# conector_driver.net
KiCad netlist of a schematic drawn in EAGLE
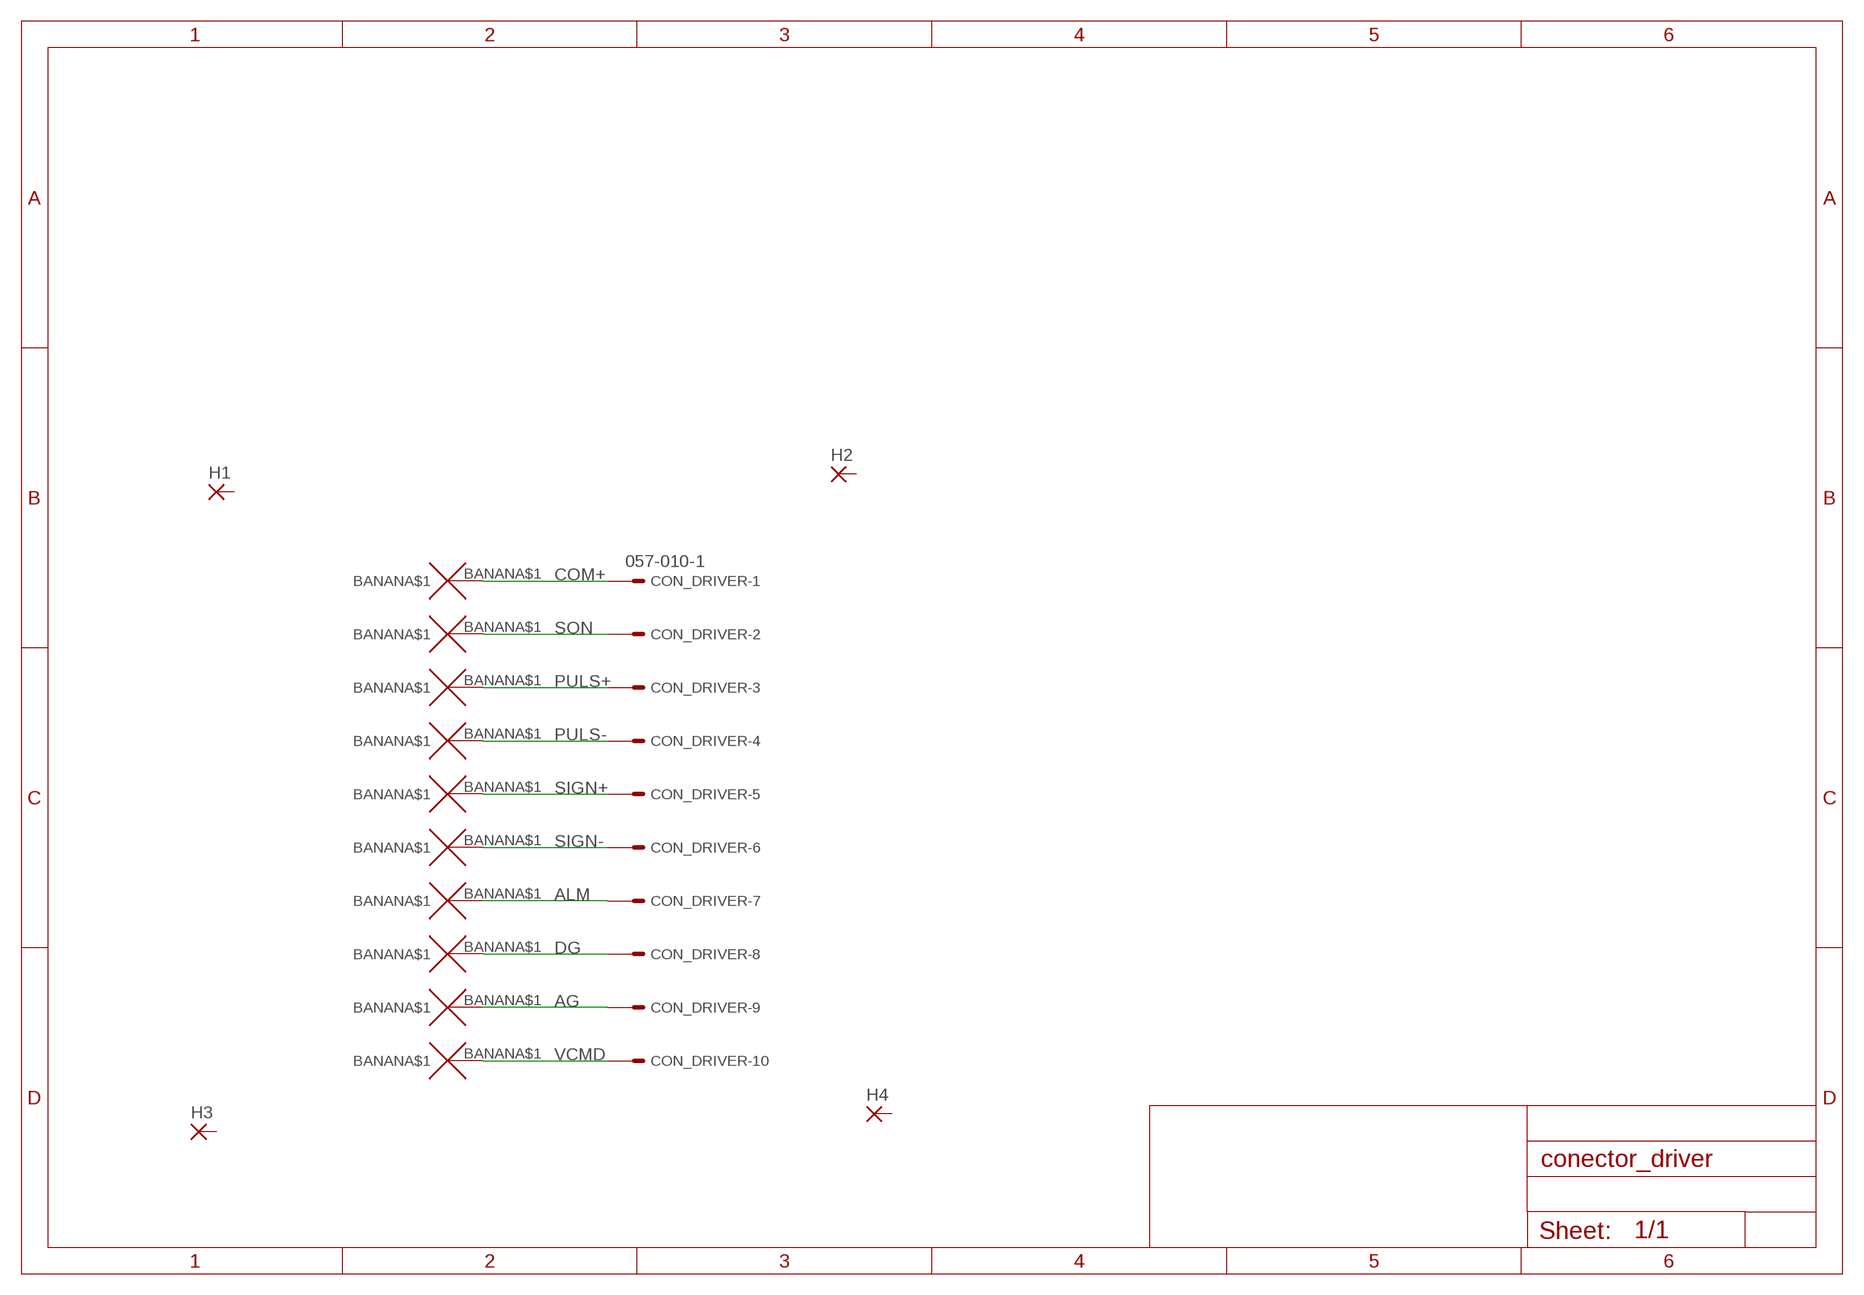
[diagram p0: schematic, sheet 1]

(export (version "E")
  (design (tool "Eeschema 10.0.6"))
  (components
    (comp (ref "AG")
      (value "BANANA")
      (footprint "eagle-import:BANANA")
      (libsource (lib "eagle-import") (part "BANANA"))
    )
    (comp (ref "ALM")
      (value "BANANA")
      (footprint "eagle-import:BANANA")
      (libsource (lib "eagle-import") (part "BANANA"))
    )
    (comp (ref "COM+")
      (value "BANANA")
      (footprint "eagle-import:BANANA")
      (libsource (lib "eagle-import") (part "BANANA"))
    )
    (comp (ref "CON_DRIVER")
      (value "057-010-1")
      (footprint "eagle-import:057-010-1")
      (libsource (lib "eagle-import") (part "057-010-1"))
    )
    (comp (ref "DG")
      (value "BANANA")
      (footprint "eagle-import:BANANA")
      (libsource (lib "eagle-import") (part "BANANA"))
    )
    (comp (ref "H1")
      (value "3,81/1,4")
      (footprint "eagle-import:3,81_1,4")
      (libsource (lib "eagle-import") (part "3,81/1,4"))
    )
    (comp (ref "H2")
      (value "3,81/1,4")
      (footprint "eagle-import:3,81_1,4")
      (libsource (lib "eagle-import") (part "3,81/1,4"))
    )
    (comp (ref "H3")
      (value "3,81/1,4")
      (footprint "eagle-import:3,81_1,4")
      (libsource (lib "eagle-import") (part "3,81/1,4"))
    )
    (comp (ref "H4")
      (value "3,81/1,4")
      (footprint "eagle-import:3,81_1,4")
      (libsource (lib "eagle-import") (part "3,81/1,4"))
    )
    (comp (ref "PULS+")
      (value "BANANA")
      (footprint "eagle-import:BANANA")
      (libsource (lib "eagle-import") (part "BANANA"))
    )
    (comp (ref "PULS-")
      (value "BANANA")
      (footprint "eagle-import:BANANA")
      (libsource (lib "eagle-import") (part "BANANA"))
    )
    (comp (ref "SIGN+")
      (value "BANANA")
      (footprint "eagle-import:BANANA")
      (libsource (lib "eagle-import") (part "BANANA"))
    )
    (comp (ref "SIGN-")
      (value "BANANA")
      (footprint "eagle-import:BANANA")
      (libsource (lib "eagle-import") (part "BANANA"))
    )
    (comp (ref "SON")
      (value "BANANA")
      (footprint "eagle-import:BANANA")
      (libsource (lib "eagle-import") (part "BANANA"))
    )
    (comp (ref "VCMD")
      (value "BANANA")
      (footprint "eagle-import:BANANA")
      (libsource (lib "eagle-import") (part "BANANA"))
    )
  )
  (nets
    (net (code "1") (name "/AG") (class "Default")
      (node (ref "AG") (pin "BANANA$1") (pinfunction "BANANA$1_BANANA$1") (pintype "bidirectional"))
      (node (ref "CON_DRIVER") (pin "9") (pinfunction "S_9") (pintype "passive"))
    )
    (net (code "2") (name "/ALM") (class "Default")
      (node (ref "ALM") (pin "BANANA$1") (pinfunction "BANANA$1_BANANA$1") (pintype "bidirectional"))
      (node (ref "CON_DRIVER") (pin "7") (pinfunction "S_7") (pintype "passive"))
    )
    (net (code "3") (name "/COM+") (class "Default")
      (node (ref "COM+") (pin "BANANA$1") (pinfunction "BANANA$1_BANANA$1") (pintype "bidirectional"))
      (node (ref "CON_DRIVER") (pin "1") (pinfunction "S_1") (pintype "passive"))
    )
    (net (code "4") (name "/DG") (class "Default")
      (node (ref "CON_DRIVER") (pin "8") (pinfunction "S_8") (pintype "passive"))
      (node (ref "DG") (pin "BANANA$1") (pinfunction "BANANA$1_BANANA$1") (pintype "bidirectional"))
    )
    (net (code "5") (name "/PULS+") (class "Default")
      (node (ref "CON_DRIVER") (pin "3") (pinfunction "S_3") (pintype "passive"))
      (node (ref "PULS+") (pin "BANANA$1") (pinfunction "BANANA$1_BANANA$1") (pintype "bidirectional"))
    )
    (net (code "6") (name "/PULS-") (class "Default")
      (node (ref "CON_DRIVER") (pin "4") (pinfunction "S_4") (pintype "passive"))
      (node (ref "PULS-") (pin "BANANA$1") (pinfunction "BANANA$1_BANANA$1") (pintype "bidirectional"))
    )
    (net (code "7") (name "/SIGN+") (class "Default")
      (node (ref "CON_DRIVER") (pin "5") (pinfunction "S_5") (pintype "passive"))
      (node (ref "SIGN+") (pin "BANANA$1") (pinfunction "BANANA$1_BANANA$1") (pintype "bidirectional"))
    )
    (net (code "8") (name "/SIGN-") (class "Default")
      (node (ref "CON_DRIVER") (pin "6") (pinfunction "S_6") (pintype "passive"))
      (node (ref "SIGN-") (pin "BANANA$1") (pinfunction "BANANA$1_BANANA$1") (pintype "bidirectional"))
    )
    (net (code "9") (name "/SON") (class "Default")
      (node (ref "CON_DRIVER") (pin "2") (pinfunction "S_2") (pintype "passive"))
      (node (ref "SON") (pin "BANANA$1") (pinfunction "BANANA$1_BANANA$1") (pintype "bidirectional"))
    )
    (net (code "10") (name "/VCMD") (class "Default")
      (node (ref "CON_DRIVER") (pin "10") (pinfunction "S_10") (pintype "passive"))
      (node (ref "VCMD") (pin "BANANA$1") (pinfunction "BANANA$1_BANANA$1") (pintype "bidirectional"))
    )
    (net (code "11") (name "unconnected-(H1-P-Pad1)") (class "Default")
      (node (ref "H1") (pin "1") (pinfunction "P_1") (pintype "passive"))
    )
    (net (code "12") (name "unconnected-(H2-P-Pad1)") (class "Default")
      (node (ref "H2") (pin "1") (pinfunction "P_1") (pintype "passive"))
    )
    (net (code "13") (name "unconnected-(H3-P-Pad1)") (class "Default")
      (node (ref "H3") (pin "1") (pinfunction "P_1") (pintype "passive"))
    )
    (net (code "14") (name "unconnected-(H4-P-Pad1)") (class "Default")
      (node (ref "H4") (pin "1") (pinfunction "P_1") (pintype "passive"))
    )
  )
)
